# Fatigue_V1_00.net
KiCad netlist of a schematic drawn in Altium Designer
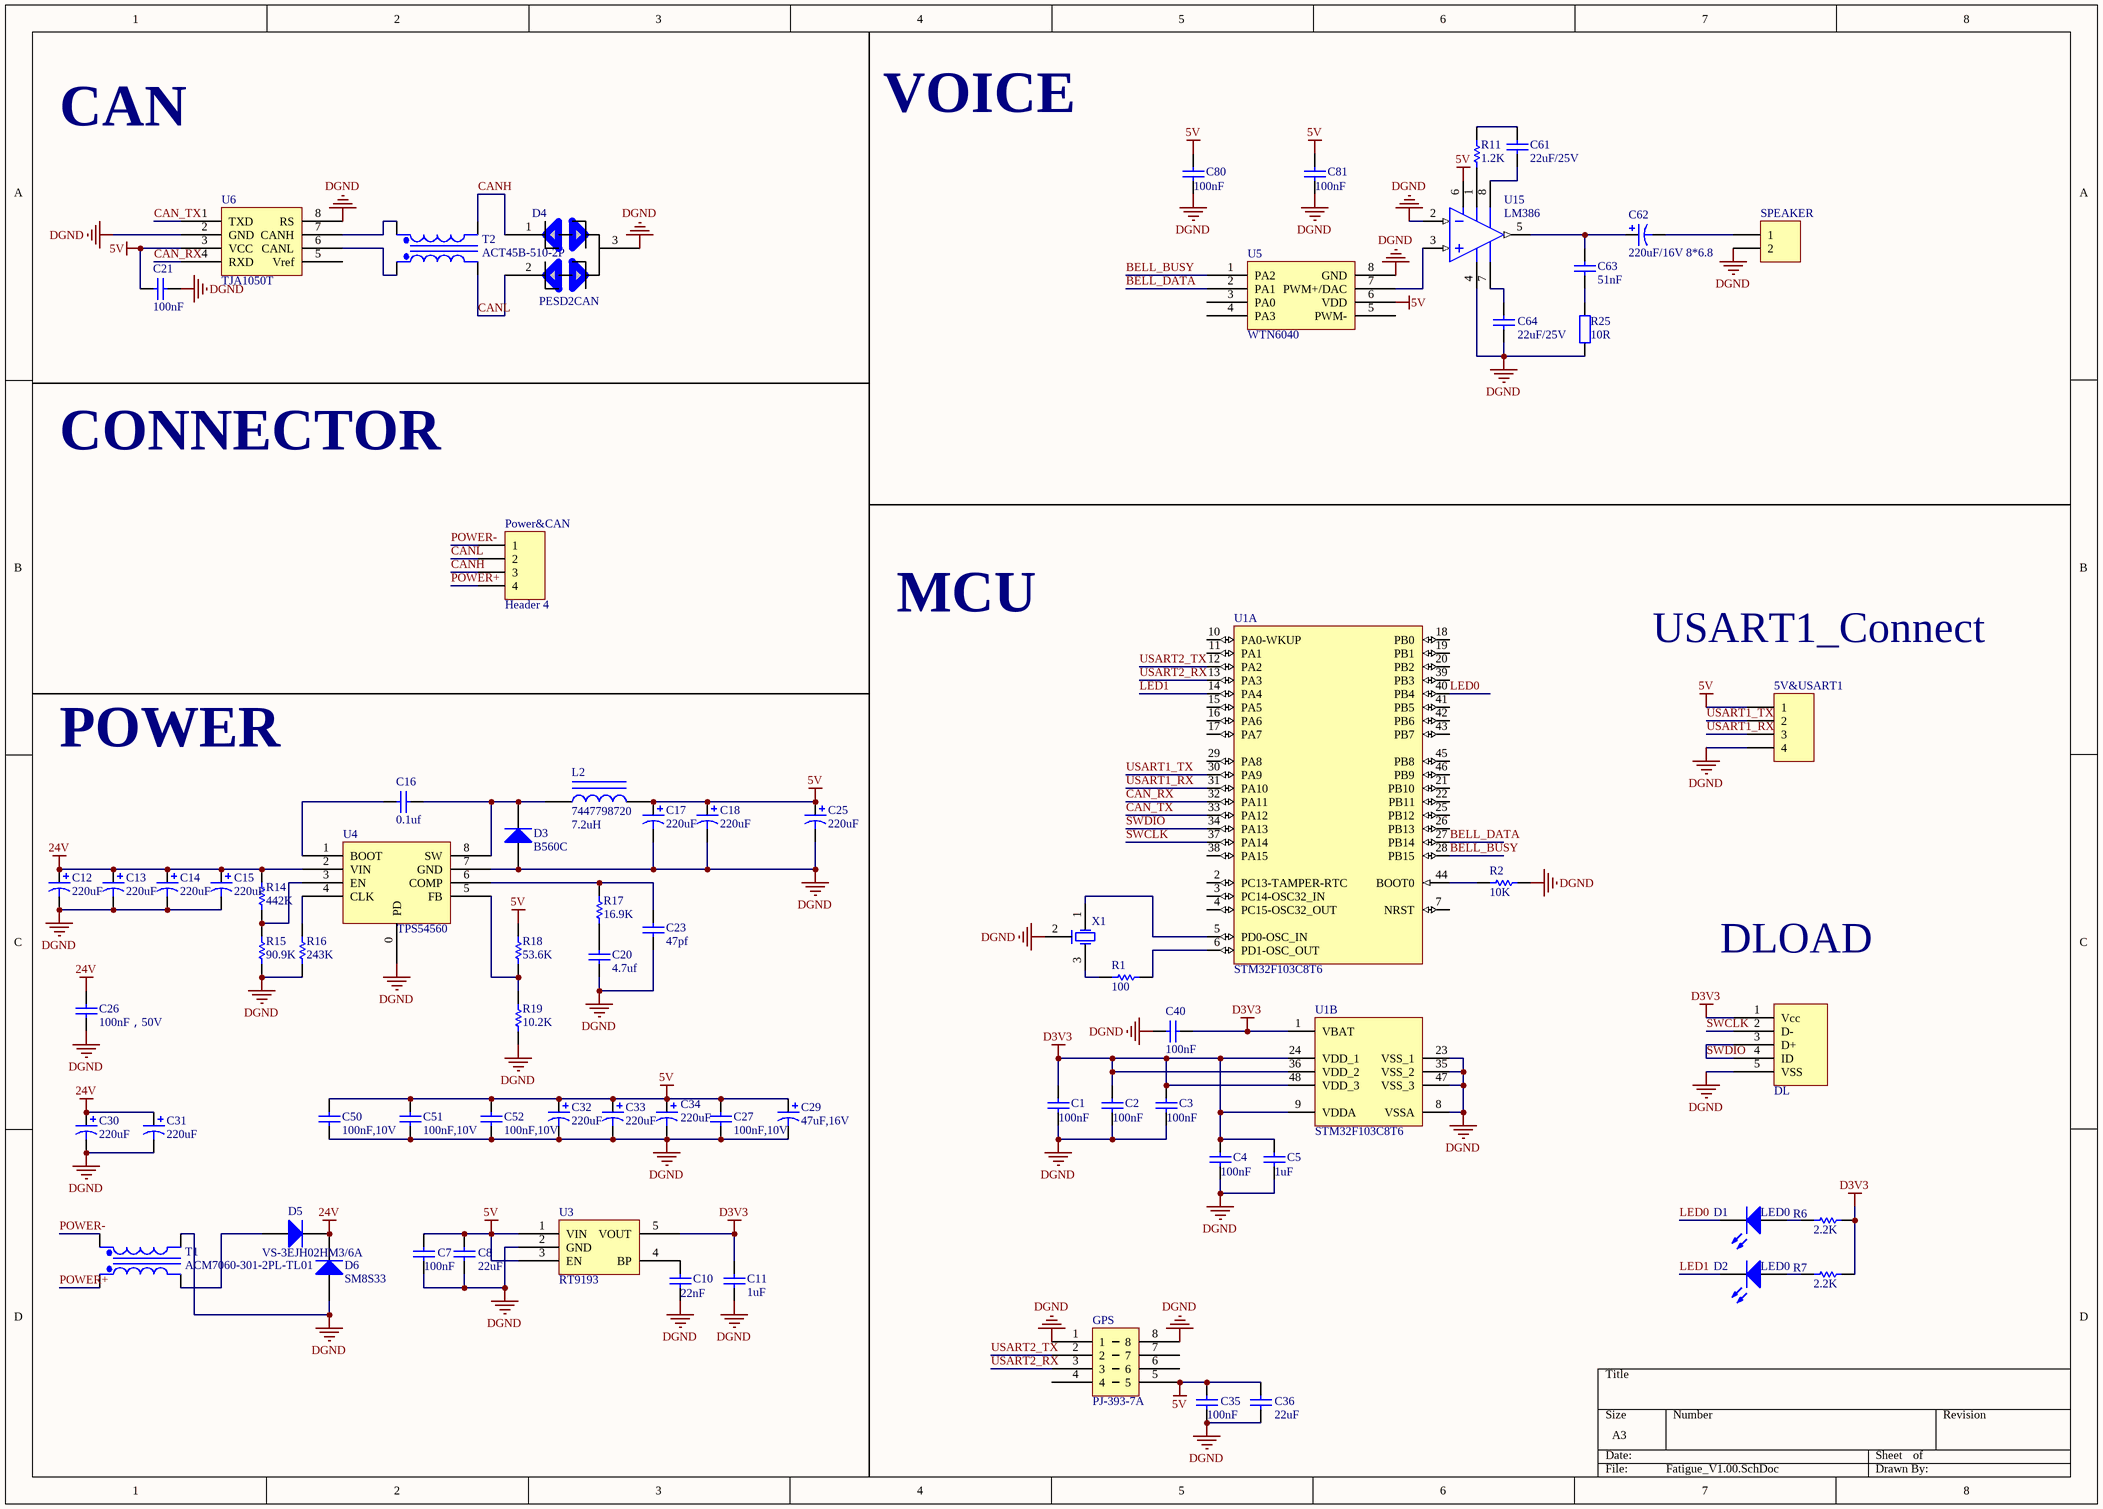
[diagram p0: Fatigue_V1.00.SchDoc]

(export (version "E")
  (design (tool "Eeschema 10.0.6"))
  (components
    (comp (ref "5V&USART1")
      (value "TEST_USART2")
      (footprint "HDR1X4")
      (description "Header, 4-Pin")
      (fields (field (name "PUBLISHER") "Altium Limited"))
      (libsource (lib "Miscellaneous Connectors") (part "Header 4"))
    )
    (comp (ref "C1")
      (value "100nF")
      (footprint "BinFeng:0402")
      (description "Capacitor")
      (fields (field (name "PUBLISHER") "Altium Limited"))
      (libsource (lib "Miscellaneous Devices") (part "Cap"))
    )
    (comp (ref "C2")
      (value "100nF")
      (footprint "BinFeng:0402")
      (description "Capacitor")
      (fields (field (name "PUBLISHER") "Altium Limited"))
      (libsource (lib "Miscellaneous Devices") (part "Cap"))
    )
    (comp (ref "C3")
      (value "100nF")
      (footprint "BinFeng:0402")
      (description "Capacitor")
      (fields (field (name "PUBLISHER") "Altium Limited"))
      (libsource (lib "Miscellaneous Devices") (part "Cap"))
    )
    (comp (ref "C4")
      (value "100nF")
      (footprint "BinFeng:0402")
      (description "Capacitor")
      (fields (field (name "PUBLISHER") "Altium Limited"))
      (libsource (lib "Miscellaneous Devices") (part "Cap"))
    )
    (comp (ref "C5")
      (value "1uF")
      (footprint "BinFeng:0603")
      (description "Capacitor")
      (fields (field (name "PUBLISHER") "Altium Limited"))
      (libsource (lib "Miscellaneous Devices") (part "Cap"))
    )
    (comp (ref "C7")
      (value "100nF")
      (footprint "BinFeng:0402")
      (description "Capacitor,100V")
      (fields (field (name "PUBLISHER") "Altium Limited"))
      (libsource (lib "Miscellaneous Devices") (part "Cap"))
    )
    (comp (ref "C8")
      (value "22uF")
      (footprint "0805")
      (description "Capacitor")
      (fields (field (name "PUBLISHER") "Altium Limited"))
      (libsource (lib "Miscellaneous Devices") (part "Cap"))
    )
    (comp (ref "C10")
      (value "22nF")
      (footprint "BinFeng:0402")
      (description "Capacitor")
      (fields (field (name "PUBLISHER") "Altium Limited"))
      (libsource (lib "Miscellaneous Devices") (part "Cap"))
    )
    (comp (ref "C11")
      (value "1uF")
      (footprint "BinFeng:0603")
      (description "Capacitor")
      (fields (field (name "PUBLISHER") "Altium Limited"))
      (libsource (lib "Miscellaneous Devices") (part "Cap"))
    )
    (comp (ref "C12")
      (value "220uF")
      (footprint "cap_pol_8*10.2")
      (description "Polarized Capacitor (Radial)")
      (fields (field (name "PUBLISHER") "Altium Limited"))
      (libsource (lib "Miscellaneous Devices") (part "Cap Pol1"))
    )
    (comp (ref "C13")
      (value "220uF")
      (footprint "cap_pol_8*10.2")
      (description "Polarized Capacitor (Radial)")
      (fields (field (name "PUBLISHER") "Altium Limited"))
      (libsource (lib "Miscellaneous Devices") (part "Cap Pol1"))
    )
    (comp (ref "C14")
      (value "220uF")
      (footprint "cap_pol_8*10.2")
      (description "Polarized Capacitor (Radial)")
      (fields (field (name "PUBLISHER") "Altium Limited"))
      (libsource (lib "Miscellaneous Devices") (part "Cap Pol1"))
    )
    (comp (ref "C15")
      (value "220uF")
      (footprint "cap_pol_8*10.2")
      (description "Polarized Capacitor (Radial)")
      (fields (field (name "PUBLISHER") "Altium Limited"))
      (libsource (lib "Miscellaneous Devices") (part "Cap Pol1"))
    )
    (comp (ref "C16")
      (value "0.1uf")
      (footprint "0603")
      (description "Capacitor")
      (fields (field (name "PUBLISHER") "Altium Limited"))
      (libsource (lib "Miscellaneous Devices") (part "Cap"))
    )
    (comp (ref "C17")
      (value "220uF")
      (footprint "cap_pol_8*10.2")
      (description "Polarized Capacitor (Radial)")
      (fields (field (name "PUBLISHER") "Altium Limited"))
      (libsource (lib "Miscellaneous Devices") (part "Cap Pol1"))
    )
    (comp (ref "C18")
      (value "220uF")
      (footprint "cap_pol_8*10.2")
      (description "Polarized Capacitor (Radial)")
      (fields (field (name "PUBLISHER") "Altium Limited"))
      (libsource (lib "Miscellaneous Devices") (part "Cap Pol1"))
    )
    (comp (ref "C20")
      (value "4.7uf")
      (footprint "0603")
      (description "Capacitor")
      (fields (field (name "PUBLISHER") "Altium Limited"))
      (libsource (lib "Miscellaneous Devices") (part "Cap"))
    )
    (comp (ref "C21")
      (value "100nF")
      (footprint "BinFeng:0402")
      (description "Capacitor")
      (fields (field (name "PUBLISHER") "Altium Limited"))
      (libsource (lib "Miscellaneous Devices") (part "Cap"))
    )
    (comp (ref "C23")
      (value "47pf")
      (footprint "0603")
      (description "Capacitor")
      (fields (field (name "PUBLISHER") "Altium Limited"))
      (libsource (lib "Miscellaneous Devices") (part "Cap"))
    )
    (comp (ref "C25")
      (value "220uF")
      (footprint "cap_pol_8*10.2")
      (description "Polarized Capacitor (Radial)")
      (fields (field (name "PUBLISHER") "Altium Limited"))
      (libsource (lib "Miscellaneous Devices") (part "Cap Pol1"))
    )
    (comp (ref "C26")
      (value "100nF，50V")
      (footprint "BinFeng:0603")
      (description "Capacitor")
      (fields (field (name "PUBLISHER") "Altium Limited"))
      (libsource (lib "Miscellaneous Devices") (part "Cap"))
    )
    (comp (ref "C27")
      (value "100nF,10V")
      (footprint "BinFeng:0402")
      (description "Capacitor")
      (fields (field (name "PUBLISHER") "Altium Limited"))
      (libsource (lib "Miscellaneous Devices") (part "Cap"))
    )
    (comp (ref "C29")
      (value "47uF,16V")
      (footprint "6032_pol")
      (description "Polarized Capacitor (Radial)")
      (fields (field (name "PUBLISHER") "Altium Limited"))
      (libsource (lib "Miscellaneous Devices") (part "Cap Pol1"))
    )
    (comp (ref "C30")
      (value "220uF")
      (footprint "cap_pol_8*10.2")
      (description "Polarized Capacitor (Radial)")
      (fields (field (name "PUBLISHER") "Altium Limited"))
      (libsource (lib "Miscellaneous Devices") (part "Cap Pol1"))
    )
    (comp (ref "C31")
      (value "220uF")
      (footprint "cap_pol_8*10.2")
      (description "Polarized Capacitor (Radial)")
      (fields (field (name "PUBLISHER") "Altium Limited"))
      (libsource (lib "Miscellaneous Devices") (part "Cap Pol1"))
    )
    (comp (ref "C32")
      (value "220uF")
      (footprint "cap_pol_8*10.2")
      (description "Polarized Capacitor (Radial)")
      (fields (field (name "PUBLISHER") "Altium Limited"))
      (libsource (lib "Miscellaneous Devices") (part "Cap Pol1"))
    )
    (comp (ref "C33")
      (value "220uF")
      (footprint "cap_pol_8*10.2")
      (description "Polarized Capacitor (Radial)")
      (fields (field (name "PUBLISHER") "Altium Limited"))
      (libsource (lib "Miscellaneous Devices") (part "Cap Pol1"))
    )
    (comp (ref "C34")
      (value "220uF")
      (footprint "cap_pol_8*10.2")
      (description "Polarized Capacitor (Radial)")
      (fields (field (name "PUBLISHER") "Altium Limited"))
      (libsource (lib "Miscellaneous Devices") (part "Cap Pol1"))
    )
    (comp (ref "C35")
      (value "100nF")
      (footprint "BinFeng:0402")
      (description "Capacitor,100V")
      (fields (field (name "PUBLISHER") "Altium Limited"))
      (libsource (lib "Miscellaneous Devices") (part "Cap"))
    )
    (comp (ref "C36")
      (value "22uF")
      (footprint "0805")
      (description "Capacitor")
      (fields (field (name "PUBLISHER") "Altium Limited"))
      (libsource (lib "Miscellaneous Devices") (part "Cap"))
    )
    (comp (ref "C40")
      (value "100nF")
      (footprint "BinFeng:0402")
      (description "Capacitor")
      (fields (field (name "PUBLISHER") "Altium Limited"))
      (libsource (lib "Miscellaneous Devices") (part "Cap"))
    )
    (comp (ref "C50")
      (value "100nF,10V")
      (footprint "BinFeng:0402")
      (description "Capacitor")
      (fields (field (name "PUBLISHER") "Altium Limited"))
      (libsource (lib "Miscellaneous Devices") (part "Cap"))
    )
    (comp (ref "C51")
      (value "100nF,10V")
      (footprint "BinFeng:0402")
      (description "Capacitor")
      (fields (field (name "PUBLISHER") "Altium Limited"))
      (libsource (lib "Miscellaneous Devices") (part "Cap"))
    )
    (comp (ref "C52")
      (value "100nF,10V")
      (footprint "BinFeng:0402")
      (description "Capacitor")
      (fields (field (name "PUBLISHER") "Altium Limited"))
      (libsource (lib "Miscellaneous Devices") (part "Cap"))
    )
    (comp (ref "C61")
      (value "22uF/25V")
      (footprint "0805")
      (description "Capacitor")
      (fields (field (name "PUBLISHER") "Altium Limited"))
      (libsource (lib "Miscellaneous Devices") (part "Cap"))
    )
    (comp (ref "C62")
      (value "220uF/16V 8*6.8")
      (footprint "cap_pol_8*10.2")
      (description "Polarized Capacitor (Radial)")
      (fields (field (name "PUBLISHER") "Altium Limited"))
      (libsource (lib "Miscellaneous Devices") (part "Cap Pol1"))
    )
    (comp (ref "C63")
      (value "51nF")
      (footprint "BinFeng:0402")
      (description "Capacitor")
      (fields (field (name "PUBLISHER") "Altium Limited"))
      (libsource (lib "Miscellaneous Devices") (part "Cap"))
    )
    (comp (ref "C64")
      (value "22uF/25V")
      (footprint "0805")
      (description "Capacitor")
      (fields (field (name "PUBLISHER") "Altium Limited"))
      (libsource (lib "Miscellaneous Devices") (part "Cap"))
    )
    (comp (ref "C80")
      (value "100nF")
      (footprint "BinFeng:0402")
      (description "Capacitor")
      (fields (field (name "PUBLISHER") "Altium Limited"))
      (libsource (lib "Miscellaneous Devices") (part "Cap"))
    )
    (comp (ref "C81")
      (value "100nF")
      (footprint "BinFeng:0402")
      (description "Capacitor")
      (fields (field (name "PUBLISHER") "Altium Limited"))
      (libsource (lib "Miscellaneous Devices") (part "Cap"))
    )
    (comp (ref "D1")
      (value "LED0")
      (footprint "1206_LED")
      (description "green LED")
      (fields (field (name "PUBLISHER") "Altium Limited"))
      (libsource (lib "Miscellaneous Devices") (part "LED0"))
    )
    (comp (ref "D2")
      (value "LED0")
      (footprint "1206_LED")
      (description "green LED")
      (fields (field (name "PUBLISHER") "Altium Limited"))
      (libsource (lib "Miscellaneous Devices") (part "LED0"))
    )
    (comp (ref "D3")
      (value "B560C")
      (footprint "BinFeng:SMC")
      (description "1 Amp General Purpose Rectifier")
      (fields (field (name "PUBLISHER") "Altium Limited"))
      (libsource (lib "Miscellaneous Devices") (part "Diode 1N4007"))
    )
    (comp (ref "D4")
      (value "PESD2CAN")
      (footprint "SOT23")
      (libsource (lib "BinFeng_Connectors") (part "PESD1CAN"))
    )
    (comp (ref "D5")
      (value "VS-3EJH02HM3/6A")
      (footprint "back:B290")
      (description "1 Amp General Purpose Rectifier")
      (fields (field (name "PUBLISHER") "Altium Limited"))
      (libsource (lib "Miscellaneous Devices") (part "Diode 1N4007"))
    )
    (comp (ref "D6")
      (value "SM8S33")
      (footprint "SM8S")
      (description "1 Amp General Purpose Rectifier")
      (fields (field (name "PUBLISHER") "Altium Limited"))
      (libsource (lib "Miscellaneous Devices") (part "Diode 1N4007"))
    )
    (comp (ref "DL")
      (value "USB_5pin")
      (footprint "USBmicro_B")
      (libsource (lib "BinFeng_Connectors") (part "USB_5pin"))
    )
    (comp (ref "GPS")
      (value "PJ-393-7A")
      (footprint "3.5mm earphone slot")
      (libsource (lib "BinFeng_IC") (part "3.5mm earphone slot"))
    )
    (comp (ref "L2")
      (value "7447798720")
      (footprint "1064")
      (description "Magnetic-Core Inductor")
      (fields (field (name "ALTIUM_VALUE") "7.2uH") (field (name "PUBLISHER") "Altium Limited"))
      (libsource (lib "Miscellaneous Devices") (part "Inductor Iron"))
    )
    (comp (ref "Power&CAN")
      (value "Header 4")
      (footprint "HDR1X4")
      (description "Header, 4-Pin")
      (fields (field (name "PUBLISHER") "Altium Limited"))
      (libsource (lib "Miscellaneous Connectors") (part "Header 4"))
    )
    (comp (ref "R1")
      (value "100")
      (footprint "BinFeng:0402")
      (description "Resistor")
      (fields (field (name "PUBLISHER") "Altium Limited"))
      (libsource (lib "Miscellaneous Devices") (part "Res1"))
    )
    (comp (ref "R2")
      (value "10K")
      (footprint "BinFeng:0402")
      (description "Resistor")
      (fields (field (name "PUBLISHER") "Altium Limited"))
      (libsource (lib "Miscellaneous Devices") (part "Res1"))
    )
    (comp (ref "R6")
      (value "2.2K")
      (footprint "BinFeng:0402")
      (description "Resistor")
      (fields (field (name "PUBLISHER") "Altium Limited"))
      (libsource (lib "Miscellaneous Devices") (part "Res1"))
    )
    (comp (ref "R7")
      (value "2.2K")
      (footprint "BinFeng:0402")
      (description "Resistor")
      (fields (field (name "PUBLISHER") "Altium Limited"))
      (libsource (lib "Miscellaneous Devices") (part "Res1"))
    )
    (comp (ref "R11")
      (value "1.2K")
      (footprint "BinFeng:0402")
      (description "Semiconductor Resistor")
      (fields (field (name "PUBLISHER") "Altium Limited"))
      (libsource (lib "Miscellaneous Devices") (part "Res Semi"))
    )
    (comp (ref "R14")
      (value "442K")
      (footprint "back:0603")
      (description "Resistor")
      (fields (field (name "PUBLISHER") "Altium Limited"))
      (libsource (lib "Miscellaneous Devices") (part "Res1"))
    )
    (comp (ref "R15")
      (value "90.9K")
      (footprint "back:0603")
      (description "Resistor")
      (fields (field (name "PUBLISHER") "Altium Limited"))
      (libsource (lib "Miscellaneous Devices") (part "Res1"))
    )
    (comp (ref "R16")
      (value "243K")
      (footprint "back:0603")
      (description "Resistor")
      (fields (field (name "PUBLISHER") "Altium Limited"))
      (libsource (lib "Miscellaneous Devices") (part "Res1"))
    )
    (comp (ref "R17")
      (value "16.9K")
      (footprint "back:0603")
      (description "Resistor")
      (fields (field (name "PUBLISHER") "Altium Limited"))
      (libsource (lib "Miscellaneous Devices") (part "Res1"))
    )
    (comp (ref "R18")
      (value "53.6K")
      (footprint "back:0603")
      (description "Resistor")
      (fields (field (name "PUBLISHER") "Altium Limited"))
      (libsource (lib "Miscellaneous Devices") (part "Res1"))
    )
    (comp (ref "R19")
      (value "10.2K")
      (footprint "back:0603")
      (description "Resistor")
      (fields (field (name "PUBLISHER") "Altium Limited"))
      (libsource (lib "Miscellaneous Devices") (part "Res1"))
    )
    (comp (ref "R25")
      (value "10R")
      (footprint "BinFeng:0402")
      (description "Resistor")
      (fields (field (name "PUBLISHER") "Altium Limited"))
      (libsource (lib "Miscellaneous Devices") (part "Res2"))
    )
    (comp (ref "SPEAKER")
      (value "SPEAKER")
      (footprint "HDR1X2")
      (description "Header, 2-Pin")
      (fields (field (name "PUBLISHER") "Altium Limited"))
      (libsource (lib "Miscellaneous Connectors") (part "Header 2"))
    )
    (comp (ref "T1")
      (value "ACM7060-301-2PL-TL01")
      (footprint "ACM7060-301-2P-TL01")
      (description "Transformer (Equivalent Circuit Model)")
      (fields (field (name "PUBLISHER") "Altium Limited"))
      (libsource (lib "Miscellaneous Devices") (part "Trans Eq"))
    )
    (comp (ref "T2")
      (value "ACT45B-510-2P")
      (footprint "ACT45B-510-2P")
      (description "Transformer (Equivalent Circuit Model)")
      (fields (field (name "PUBLISHER") "Altium Limited"))
      (libsource (lib "Miscellaneous Devices") (part "Trans Eq"))
    )
    (comp (ref "U1")
      (value "STM32F103C8T6")
      (footprint "STM-LQFP48_N")
      (libsource (lib "STMicroelectronics STM32 F1") (part "STM32F103C8T6"))
    )
    (comp (ref "U3") (value "RT9193") (footprint "SOT-23-5") (libsource (lib "BinFeng_IC") (part "RT9193")))
    (comp (ref "U4") (value "TPS54560") (footprint "HSOIC_8") (libsource (lib "MySchlib1") (part "TPS54560")))
    (comp (ref "U5") (value "WTN6040") (footprint "SO8") (libsource (lib "Schlib3") (part "WTN6040")))
    (comp (ref "U6")
      (value "TJA1050T")
      (footprint "SO8")
      (description "CAN Tranceiver")
      (libsource (lib "BinFeng_IC") (part "TJA1050T"))
    )
    (comp (ref "U15") (value "LM386") (footprint "SO8") (libsource (lib "My_Schlib") (part "LM386_1")))
    (comp (ref "X1") (value "8M smd") (footprint "8M") (libsource (lib "Schlib1") (part "8M smd")))
  )
  (nets
    (net (code "1") (name "/BELL_BUSY") (class "Default")
      (node (ref "U1") (pin "28") (pinfunction "PB15_28") (pintype "bidirectional"))
      (node (ref "U5") (pin "1") (pinfunction "PA2_1") (pintype "passive"))
    )
    (net (code "2") (name "/BELL_DATA") (class "Default")
      (node (ref "U1") (pin "27") (pinfunction "PB14_27") (pintype "bidirectional"))
      (node (ref "U5") (pin "2") (pinfunction "PA1_2") (pintype "passive"))
    )
    (net (code "3") (name "/CANH") (class "Default")
      (node (ref "D4") (pin "1") (pinfunction "11_1") (pintype "passive"))
      (node (ref "Power&CAN") (pin "3") (pinfunction "3_3") (pintype "passive"))
      (node (ref "T2") (pin "4") (pinfunction "Sec-_4") (pintype "passive"))
    )
    (net (code "4") (name "/CANL") (class "Default")
      (node (ref "D4") (pin "2") (pinfunction "12_2") (pintype "passive"))
      (node (ref "Power&CAN") (pin "2") (pinfunction "2_2") (pintype "passive"))
      (node (ref "T2") (pin "2") (pinfunction "Pri-_2") (pintype "passive"))
    )
    (net (code "5") (name "/CAN_RX") (class "Default")
      (node (ref "U1") (pin "32") (pinfunction "PA11_32") (pintype "bidirectional"))
      (node (ref "U6") (pin "4") (pinfunction "RXD_4") (pintype "passive"))
    )
    (net (code "6") (name "/CAN_TX") (class "Default")
      (node (ref "U1") (pin "33") (pinfunction "PA12_33") (pintype "bidirectional"))
      (node (ref "U6") (pin "1") (pinfunction "TXD_1") (pintype "passive"))
    )
    (net (code "7") (name "/LED0") (class "Default")
      (node (ref "D1") (pin "2") (pinfunction "K_2") (pintype "passive"))
      (node (ref "U1") (pin "40") (pinfunction "PB4_40") (pintype "bidirectional"))
    )
    (net (code "8") (name "/LED1") (class "Default")
      (node (ref "D2") (pin "2") (pinfunction "K_2") (pintype "passive"))
      (node (ref "U1") (pin "14") (pinfunction "PA4_14") (pintype "bidirectional"))
    )
    (net (code "9") (name "/POWER+") (class "Default")
      (node (ref "Power&CAN") (pin "4") (pinfunction "4_4") (pintype "passive"))
      (node (ref "T1") (pin "1") (pinfunction "Pri+_1") (pintype "passive"))
    )
    (net (code "10") (name "/POWER-") (class "Default")
      (node (ref "Power&CAN") (pin "1") (pinfunction "1_1") (pintype "passive"))
      (node (ref "T1") (pin "3") (pinfunction "Sec+_3") (pintype "passive"))
    )
    (net (code "11") (name "/SWCLK") (class "Default")
      (node (ref "DL") (pin "2") (pinfunction "D-_2") (pintype "passive"))
      (node (ref "U1") (pin "37") (pinfunction "PA14_37") (pintype "bidirectional"))
    )
    (net (code "12") (name "/SWDIO") (class "Default")
      (node (ref "DL") (pin "3") (pinfunction "D+_3") (pintype "passive"))
      (node (ref "DL") (pin "4") (pinfunction "ID_4") (pintype "passive"))
      (node (ref "U1") (pin "34") (pinfunction "PA13_34") (pintype "bidirectional"))
    )
    (net (code "13") (name "/USART1_RX") (class "Default")
      (node (ref "5V&USART1") (pin "3") (pinfunction "3_3") (pintype "passive"))
      (node (ref "U1") (pin "31") (pinfunction "PA10_31") (pintype "bidirectional"))
    )
    (net (code "14") (name "/USART1_TX") (class "Default")
      (node (ref "5V&USART1") (pin "2") (pinfunction "2_2") (pintype "passive"))
      (node (ref "U1") (pin "30") (pinfunction "PA9_30") (pintype "bidirectional"))
    )
    (net (code "15") (name "/USART2_RX") (class "Default")
      (node (ref "GPS") (pin "3") (pinfunction "3_3") (pintype "passive"))
      (node (ref "U1") (pin "13") (pinfunction "PA3_13") (pintype "bidirectional"))
    )
    (net (code "16") (name "/USART2_TX") (class "Default")
      (node (ref "GPS") (pin "2") (pinfunction "2_2") (pintype "passive"))
      (node (ref "U1") (pin "12") (pinfunction "PA2_12") (pintype "bidirectional"))
    )
    (net (code "17") (name "5V") (class "Default")
      (node (ref "5V&USART1") (pin "1") (pinfunction "1_1") (pintype "passive"))
      (node (ref "C17") (pin "1") (pinfunction "1_1") (pintype "passive"))
      (node (ref "C18") (pin "1") (pinfunction "1_1") (pintype "passive"))
      (node (ref "C21") (pin "1") (pinfunction "1_1") (pintype "passive"))
      (node (ref "C25") (pin "1") (pinfunction "1_1") (pintype "passive"))
      (node (ref "C27") (pin "1") (pinfunction "1_1") (pintype "passive"))
      (node (ref "C29") (pin "1") (pinfunction "1_1") (pintype "passive"))
      (node (ref "C32") (pin "1") (pinfunction "1_1") (pintype "passive"))
      (node (ref "C33") (pin "1") (pinfunction "1_1") (pintype "passive"))
      (node (ref "C34") (pin "1") (pinfunction "1_1") (pintype "passive"))
      (node (ref "C35") (pin "2") (pinfunction "2_2") (pintype "passive"))
      (node (ref "C36") (pin "2") (pinfunction "2_2") (pintype "passive"))
      (node (ref "C50") (pin "1") (pinfunction "1_1") (pintype "passive"))
      (node (ref "C51") (pin "1") (pinfunction "1_1") (pintype "passive"))
      (node (ref "C52") (pin "1") (pinfunction "1_1") (pintype "passive"))
      (node (ref "C7") (pin "2") (pinfunction "2_2") (pintype "passive"))
      (node (ref "C8") (pin "2") (pinfunction "2_2") (pintype "passive"))
      (node (ref "C80") (pin "2") (pinfunction "2_2") (pintype "passive"))
      (node (ref "C81") (pin "2") (pinfunction "2_2") (pintype "passive"))
      (node (ref "GPS") (pin "5") (pinfunction "5_5") (pintype "passive"))
      (node (ref "L2") (pin "2") (pinfunction "2_2") (pintype "passive"))
      (node (ref "R18") (pin "2") (pinfunction "2_2") (pintype "passive"))
      (node (ref "U15") (pin "6") (pinfunction "OS_NUL_6") (pintype "passive"))
      (node (ref "U3") (pin "1") (pinfunction "VIN_1") (pintype "passive"))
      (node (ref "U3") (pin "3") (pinfunction "EN_3") (pintype "passive"))
      (node (ref "U5") (pin "6") (pinfunction "VDD_6") (pintype "power_in"))
      (node (ref "U6") (pin "3") (pinfunction "VCC_3") (pintype "passive"))
    )
    (net (code "18") (name "24V") (class "Default")
      (node (ref "C12") (pin "1") (pinfunction "1_1") (pintype "passive"))
      (node (ref "C13") (pin "1") (pinfunction "1_1") (pintype "passive"))
      (node (ref "C14") (pin "1") (pinfunction "1_1") (pintype "passive"))
      (node (ref "C15") (pin "1") (pinfunction "1_1") (pintype "passive"))
      (node (ref "C26") (pin "1") (pinfunction "1_1") (pintype "passive"))
      (node (ref "C30") (pin "1") (pinfunction "1_1") (pintype "passive"))
      (node (ref "C31") (pin "1") (pinfunction "1_1") (pintype "passive"))
      (node (ref "D5") (pin "2") (pinfunction "K_2") (pintype "passive"))
      (node (ref "D6") (pin "2") (pinfunction "K_2") (pintype "passive"))
      (node (ref "R14") (pin "2") (pinfunction "2_2") (pintype "passive"))
      (node (ref "U4") (pin "2") (pinfunction "VIN_2") (pintype "passive"))
    )
    (net (code "19") (name "D3V3") (class "Default")
      (node (ref "C1") (pin "2") (pinfunction "2_2") (pintype "passive"))
      (node (ref "C11") (pin "2") (pinfunction "2_2") (pintype "passive"))
      (node (ref "C2") (pin "2") (pinfunction "2_2") (pintype "passive"))
      (node (ref "C3") (pin "2") (pinfunction "2_2") (pintype "passive"))
      (node (ref "C4") (pin "2") (pinfunction "2_2") (pintype "passive"))
      (node (ref "C40") (pin "1") (pinfunction "1_1") (pintype "passive"))
      (node (ref "C5") (pin "2") (pinfunction "2_2") (pintype "passive"))
      (node (ref "DL") (pin "1") (pinfunction "Vcc_1") (pintype "passive"))
      (node (ref "R6") (pin "1") (pinfunction "1_1") (pintype "passive"))
      (node (ref "R7") (pin "1") (pinfunction "1_1") (pintype "passive"))
      (node (ref "U1") (pin "1") (pinfunction "VBAT_1") (pintype "power_in"))
      (node (ref "U1") (pin "24") (pinfunction "VDD_1_24") (pintype "power_in"))
      (node (ref "U1") (pin "36") (pinfunction "VDD_2_36") (pintype "power_in"))
      (node (ref "U1") (pin "48") (pinfunction "VDD_3_48") (pintype "power_in"))
      (node (ref "U1") (pin "9") (pinfunction "VDDA_9") (pintype "power_in"))
      (node (ref "U3") (pin "5") (pinfunction "VOUT_5") (pintype "passive"))
    )
    (net (code "20") (name "DGND") (class "Default")
      (node (ref "5V&USART1") (pin "4") (pinfunction "4_4") (pintype "passive"))
      (node (ref "C1") (pin "1") (pinfunction "1_1") (pintype "passive"))
      (node (ref "C10") (pin "1") (pinfunction "1_1") (pintype "passive"))
      (node (ref "C11") (pin "1") (pinfunction "1_1") (pintype "passive"))
      (node (ref "C12") (pin "2") (pinfunction "2_2") (pintype "passive"))
      (node (ref "C13") (pin "2") (pinfunction "2_2") (pintype "passive"))
      (node (ref "C14") (pin "2") (pinfunction "2_2") (pintype "passive"))
      (node (ref "C15") (pin "2") (pinfunction "2_2") (pintype "passive"))
      (node (ref "C17") (pin "2") (pinfunction "2_2") (pintype "passive"))
      (node (ref "C18") (pin "2") (pinfunction "2_2") (pintype "passive"))
      (node (ref "C2") (pin "1") (pinfunction "1_1") (pintype "passive"))
      (node (ref "C20") (pin "2") (pinfunction "2_2") (pintype "passive"))
      (node (ref "C21") (pin "2") (pinfunction "2_2") (pintype "passive"))
      (node (ref "C23") (pin "2") (pinfunction "2_2") (pintype "passive"))
      (node (ref "C25") (pin "2") (pinfunction "2_2") (pintype "passive"))
      (node (ref "C26") (pin "2") (pinfunction "2_2") (pintype "passive"))
      (node (ref "C27") (pin "2") (pinfunction "2_2") (pintype "passive"))
      (node (ref "C29") (pin "2") (pinfunction "2_2") (pintype "passive"))
      (node (ref "C3") (pin "1") (pinfunction "1_1") (pintype "passive"))
      (node (ref "C30") (pin "2") (pinfunction "2_2") (pintype "passive"))
      (node (ref "C31") (pin "2") (pinfunction "2_2") (pintype "passive"))
      (node (ref "C32") (pin "2") (pinfunction "2_2") (pintype "passive"))
      (node (ref "C33") (pin "2") (pinfunction "2_2") (pintype "passive"))
      (node (ref "C34") (pin "2") (pinfunction "2_2") (pintype "passive"))
      (node (ref "C35") (pin "1") (pinfunction "1_1") (pintype "passive"))
      (node (ref "C36") (pin "1") (pinfunction "1_1") (pintype "passive"))
      (node (ref "C4") (pin "1") (pinfunction "1_1") (pintype "passive"))
      (node (ref "C40") (pin "2") (pinfunction "2_2") (pintype "passive"))
      (node (ref "C5") (pin "1") (pinfunction "1_1") (pintype "passive"))
      (node (ref "C50") (pin "2") (pinfunction "2_2") (pintype "passive"))
      (node (ref "C51") (pin "2") (pinfunction "2_2") (pintype "passive"))
      (node (ref "C52") (pin "2") (pinfunction "2_2") (pintype "passive"))
      (node (ref "C64") (pin "1") (pinfunction "1_1") (pintype "passive"))
      (node (ref "C7") (pin "1") (pinfunction "1_1") (pintype "passive"))
      (node (ref "C8") (pin "1") (pinfunction "1_1") (pintype "passive"))
      (node (ref "C80") (pin "1") (pinfunction "1_1") (pintype "passive"))
      (node (ref "C81") (pin "1") (pinfunction "1_1") (pintype "passive"))
      (node (ref "D3") (pin "1") (pinfunction "A_1") (pintype "passive"))
      (node (ref "D4") (pin "3") (pinfunction "13_3") (pintype "passive"))
      (node (ref "D6") (pin "1") (pinfunction "A_1") (pintype "passive"))
      (node (ref "DL") (pin "5") (pinfunction "VSS_5") (pintype "passive"))
      (node (ref "GPS") (pin "1") (pinfunction "1_1") (pintype "passive"))
      (node (ref "GPS") (pin "8") (pinfunction "8_8") (pintype "passive"))
      (node (ref "R15") (pin "1") (pinfunction "1_1") (pintype "passive"))
      (node (ref "R16") (pin "1") (pinfunction "1_1") (pintype "passive"))
      (node (ref "R19") (pin "1") (pinfunction "1_1") (pintype "passive"))
      (node (ref "R2") (pin "2") (pinfunction "2_2") (pintype "passive"))
      (node (ref "R25") (pin "1") (pinfunction "1_1") (pintype "passive"))
      (node (ref "SPEAKER") (pin "2") (pinfunction "2_2") (pintype "passive"))
      (node (ref "T1") (pin "4") (pinfunction "Sec-_4") (pintype "passive"))
      (node (ref "U1") (pin "23") (pinfunction "VSS_1_23") (pintype "power_in"))
      (node (ref "U1") (pin "35") (pinfunction "VSS_2_35") (pintype "power_in"))
      (node (ref "U1") (pin "47") (pinfunction "VSS_3_47") (pintype "power_in"))
      (node (ref "U1") (pin "8") (pinfunction "VSSA_8") (pintype "power_in"))
      (node (ref "U15") (pin "2") (pinfunction "IN-_2") (pintype "input"))
      (node (ref "U15") (pin "4") (pinfunction "V+_4") (pintype "power_in"))
      (node (ref "U3") (pin "2") (pinfunction "GND_2") (pintype "passive"))
      (node (ref "U4") (pin "0") (pinfunction "PD_0") (pintype "passive"))
      (node (ref "U4") (pin "7") (pinfunction "GND_7") (pintype "passive"))
      (node (ref "U5") (pin "8") (pinfunction "GND_8") (pintype "power_in"))
      (node (ref "U6") (pin "2") (pinfunction "GND_2") (pintype "passive"))
      (node (ref "U6") (pin "8") (pinfunction "RS_8") (pintype "passive"))
      (node (ref "X1") (pin "2") (pinfunction "GND_2") (pintype "passive"))
    )
    (net (code "21") (name "Net-(C20-Pad1)") (class "Default")
      (node (ref "C20") (pin "1") (pinfunction "1_1") (pintype "passive"))
      (node (ref "R17") (pin "1") (pinfunction "1_1") (pintype "passive"))
    )
    (net (code "22") (name "Net-(C61-Pad1)") (class "Default")
      (node (ref "C61") (pin "1") (pinfunction "1_1") (pintype "passive"))
      (node (ref "R11") (pin "1") (pinfunction "1_1") (pintype "passive"))
    )
    (net (code "23") (name "Net-(C61-Pad2)") (class "Default")
      (node (ref "C61") (pin "2") (pinfunction "2_2") (pintype "passive"))
      (node (ref "U15") (pin "8") (pinfunction "OS_NUL_8") (pintype "passive"))
    )
    (net (code "24") (name "Net-(C62-Pad2)") (class "Default")
      (node (ref "C62") (pin "2") (pinfunction "2_2") (pintype "passive"))
      (node (ref "SPEAKER") (pin "1") (pinfunction "1_1") (pintype "passive"))
    )
    (net (code "25") (name "Net-(C63-Pad2)") (class "Default")
      (node (ref "C63") (pin "2") (pinfunction "2_2") (pintype "passive"))
      (node (ref "R25") (pin "2") (pinfunction "2_2") (pintype "passive"))
    )
    (net (code "26") (name "Net-(D1-A)") (class "Default")
      (node (ref "D1") (pin "1") (pinfunction "A_1") (pintype "passive"))
      (node (ref "R6") (pin "2") (pinfunction "2_2") (pintype "passive"))
    )
    (net (code "27") (name "Net-(D2-A)") (class "Default")
      (node (ref "D2") (pin "1") (pinfunction "A_1") (pintype "passive"))
      (node (ref "R7") (pin "2") (pinfunction "2_2") (pintype "passive"))
    )
    (net (code "28") (name "Net-(D3-K)") (class "Default")
      (node (ref "C16") (pin "1") (pinfunction "1_1") (pintype "passive"))
      (node (ref "D3") (pin "2") (pinfunction "K_2") (pintype "passive"))
      (node (ref "L2") (pin "1") (pinfunction "1_1") (pintype "passive"))
      (node (ref "U4") (pin "8") (pinfunction "SW_8") (pintype "passive"))
    )
    (net (code "29") (name "Net-(D5-A)") (class "Default")
      (node (ref "D5") (pin "1") (pinfunction "A_1") (pintype "passive"))
      (node (ref "T1") (pin "2") (pinfunction "Pri-_2") (pintype "passive"))
    )
    (net (code "30") (name "Net-(T2-Pri+)") (class "Default")
      (node (ref "T2") (pin "1") (pinfunction "Pri+_1") (pintype "passive"))
      (node (ref "U6") (pin "6") (pinfunction "CANL_6") (pintype "passive"))
    )
    (net (code "31") (name "Net-(T2-Sec+)") (class "Default")
      (node (ref "T2") (pin "3") (pinfunction "Sec+_3") (pintype "passive"))
      (node (ref "U6") (pin "7") (pinfunction "CANH_7") (pintype "passive"))
    )
    (net (code "32") (name "Net-(U1A-BOOT0)") (class "Default")
      (node (ref "R2") (pin "1") (pinfunction "1_1") (pintype "passive"))
      (node (ref "U1") (pin "44") (pinfunction "BOOT0_44") (pintype "input"))
    )
    (net (code "33") (name "Net-(U1A-PD0-OSC_IN)") (class "Default")
      (node (ref "U1") (pin "5") (pinfunction "PD0-OSC_IN_5") (pintype "bidirectional"))
      (node (ref "X1") (pin "1") (pinfunction "OSC1_1") (pintype "passive"))
    )
    (net (code "34") (name "Net-(U1A-PD1-OSC_OUT)") (class "Default")
      (node (ref "R1") (pin "2") (pinfunction "2_2") (pintype "passive"))
      (node (ref "U1") (pin "6") (pinfunction "PD1-OSC_OUT_6") (pintype "bidirectional"))
    )
    (net (code "35") (name "Net-(U3-BP)") (class "Default")
      (node (ref "C10") (pin "2") (pinfunction "2_2") (pintype "passive"))
      (node (ref "U3") (pin "4") (pinfunction "BP_4") (pintype "passive"))
    )
    (net (code "36") (name "Net-(U4-BOOT)") (class "Default")
      (node (ref "C16") (pin "2") (pinfunction "2_2") (pintype "passive"))
      (node (ref "U4") (pin "1") (pinfunction "BOOT_1") (pintype "passive"))
    )
    (net (code "37") (name "Net-(U4-CLK)") (class "Default")
      (node (ref "R16") (pin "2") (pinfunction "2_2") (pintype "passive"))
      (node (ref "U4") (pin "4") (pinfunction "CLK_4") (pintype "passive"))
    )
    (net (code "38") (name "Net-(U4-COMP)") (class "Default")
      (node (ref "C23") (pin "1") (pinfunction "1_1") (pintype "passive"))
      (node (ref "R17") (pin "2") (pinfunction "2_2") (pintype "passive"))
      (node (ref "U4") (pin "6") (pinfunction "COMP_6") (pintype "passive"))
    )
    (net (code "39") (name "Net-(U4-EN)") (class "Default")
      (node (ref "R14") (pin "1") (pinfunction "1_1") (pintype "passive"))
      (node (ref "R15") (pin "2") (pinfunction "2_2") (pintype "passive"))
      (node (ref "U4") (pin "3") (pinfunction "EN_3") (pintype "passive"))
    )
    (net (code "40") (name "Net-(U4-FB)") (class "Default")
      (node (ref "R18") (pin "1") (pinfunction "1_1") (pintype "passive"))
      (node (ref "R19") (pin "2") (pinfunction "2_2") (pintype "passive"))
      (node (ref "U4") (pin "5") (pinfunction "FB_5") (pintype "passive"))
    )
    (net (code "41") (name "Net-(U15-IN+)") (class "Default")
      (node (ref "U15") (pin "3") (pinfunction "IN+_3") (pintype "input"))
      (node (ref "U5") (pin "7") (pinfunction "PWM+/DAC_7") (pintype "passive"))
    )
    (net (code "42") (name "Net-(U15-OUT)") (class "Default")
      (node (ref "C62") (pin "1") (pinfunction "1_1") (pintype "passive"))
      (node (ref "C63") (pin "1") (pinfunction "1_1") (pintype "passive"))
      (node (ref "U15") (pin "5") (pinfunction "OUT_5") (pintype "output"))
    )
    (net (code "43") (name "Net-(U15-TAB)") (class "Default")
      (node (ref "C64") (pin "2") (pinfunction "2_2") (pintype "passive"))
      (node (ref "U15") (pin "7") (pinfunction "TAB_7") (pintype "passive"))
    )
    (net (code "44") (name "Net-(U15-V-)") (class "Default")
      (node (ref "R11") (pin "2") (pinfunction "2_2") (pintype "passive"))
      (node (ref "U15") (pin "1") (pinfunction "V-_1") (pintype "power_in"))
    )
    (net (code "45") (name "Net-(X1-OSC2)") (class "Default")
      (node (ref "R1") (pin "1") (pinfunction "1_1") (pintype "passive"))
      (node (ref "X1") (pin "3") (pinfunction "OSC2_3") (pintype "passive"))
    )
    (net (code "46") (name "unconnected-(GPS-Pad4)") (class "Default")
      (node (ref "GPS") (pin "4") (pinfunction "4_4") (pintype "passive"))
    )
    (net (code "47") (name "unconnected-(GPS-Pad6)") (class "Default")
      (node (ref "GPS") (pin "6") (pinfunction "6_6") (pintype "passive"))
    )
    (net (code "48") (name "unconnected-(GPS-Pad7)") (class "Default")
      (node (ref "GPS") (pin "7") (pinfunction "7_7") (pintype "passive"))
    )
    (net (code "49") (name "unconnected-(U1A-NRST-Pad7)") (class "Default")
      (node (ref "U1") (pin "7") (pinfunction "NRST_7") (pintype "bidirectional"))
    )
    (net (code "50") (name "unconnected-(U1A-PA0-WKUP-Pad10)") (class "Default")
      (node (ref "U1") (pin "10") (pinfunction "PA0-WKUP_10") (pintype "bidirectional"))
    )
    (net (code "51") (name "unconnected-(U1A-PA1-Pad11)") (class "Default")
      (node (ref "U1") (pin "11") (pinfunction "PA1_11") (pintype "bidirectional"))
    )
    (net (code "52") (name "unconnected-(U1A-PA5-Pad15)") (class "Default")
      (node (ref "U1") (pin "15") (pinfunction "PA5_15") (pintype "bidirectional"))
    )
    (net (code "53") (name "unconnected-(U1A-PA6-Pad16)") (class "Default")
      (node (ref "U1") (pin "16") (pinfunction "PA6_16") (pintype "bidirectional"))
    )
    (net (code "54") (name "unconnected-(U1A-PA7-Pad17)") (class "Default")
      (node (ref "U1") (pin "17") (pinfunction "PA7_17") (pintype "bidirectional"))
    )
    (net (code "55") (name "unconnected-(U1A-PA8-Pad29)") (class "Default")
      (node (ref "U1") (pin "29") (pinfunction "PA8_29") (pintype "bidirectional"))
    )
    (net (code "56") (name "unconnected-(U1A-PA15-Pad38)") (class "Default")
      (node (ref "U1") (pin "38") (pinfunction "PA15_38") (pintype "bidirectional"))
    )
    (net (code "57") (name "unconnected-(U1A-PB0-Pad18)") (class "Default")
      (node (ref "U1") (pin "18") (pinfunction "PB0_18") (pintype "bidirectional"))
    )
    (net (code "58") (name "unconnected-(U1A-PB1-Pad19)") (class "Default")
      (node (ref "U1") (pin "19") (pinfunction "PB1_19") (pintype "bidirectional"))
    )
    (net (code "59") (name "unconnected-(U1A-PB2-Pad20)") (class "Default")
      (node (ref "U1") (pin "20") (pinfunction "PB2_20") (pintype "bidirectional"))
    )
    (net (code "60") (name "unconnected-(U1A-PB3-Pad39)") (class "Default")
      (node (ref "U1") (pin "39") (pinfunction "PB3_39") (pintype "bidirectional"))
    )
    (net (code "61") (name "unconnected-(U1A-PB5-Pad41)") (class "Default")
      (node (ref "U1") (pin "41") (pinfunction "PB5_41") (pintype "bidirectional"))
    )
    (net (code "62") (name "unconnected-(U1A-PB6-Pad42)") (class "Default")
      (node (ref "U1") (pin "42") (pinfunction "PB6_42") (pintype "bidirectional"))
    )
    (net (code "63") (name "unconnected-(U1A-PB7-Pad43)") (class "Default")
      (node (ref "U1") (pin "43") (pinfunction "PB7_43") (pintype "bidirectional"))
    )
    (net (code "64") (name "unconnected-(U1A-PB8-Pad45)") (class "Default")
      (node (ref "U1") (pin "45") (pinfunction "PB8_45") (pintype "bidirectional"))
    )
    (net (code "65") (name "unconnected-(U1A-PB9-Pad46)") (class "Default")
      (node (ref "U1") (pin "46") (pinfunction "PB9_46") (pintype "bidirectional"))
    )
    (net (code "66") (name "unconnected-(U1A-PB10-Pad21)") (class "Default")
      (node (ref "U1") (pin "21") (pinfunction "PB10_21") (pintype "bidirectional"))
    )
    (net (code "67") (name "unconnected-(U1A-PB11-Pad22)") (class "Default")
      (node (ref "U1") (pin "22") (pinfunction "PB11_22") (pintype "bidirectional"))
    )
    (net (code "68") (name "unconnected-(U1A-PB12-Pad25)") (class "Default")
      (node (ref "U1") (pin "25") (pinfunction "PB12_25") (pintype "bidirectional"))
    )
    (net (code "69") (name "unconnected-(U1A-PB13-Pad26)") (class "Default")
      (node (ref "U1") (pin "26") (pinfunction "PB13_26") (pintype "bidirectional"))
    )
    (net (code "70") (name "unconnected-(U1A-PC13-TAMPER-RTC-Pad2)") (class "Default")
      (node (ref "U1") (pin "2") (pinfunction "PC13-TAMPER-RTC_2") (pintype "bidirectional"))
    )
    (net (code "71") (name "unconnected-(U1A-PC14-OSC32_IN-Pad3)") (class "Default")
      (node (ref "U1") (pin "3") (pinfunction "PC14-OSC32_IN_3") (pintype "bidirectional"))
    )
    (net (code "72") (name "unconnected-(U1A-PC15-OSC32_OUT-Pad4)") (class "Default")
      (node (ref "U1") (pin "4") (pinfunction "PC15-OSC32_OUT_4") (pintype "bidirectional"))
    )
    (net (code "73") (name "unconnected-(U5-PA0-Pad3)") (class "Default")
      (node (ref "U5") (pin "3") (pinfunction "PA0_3") (pintype "passive"))
    )
    (net (code "74") (name "unconnected-(U5-PA3-Pad4)") (class "Default")
      (node (ref "U5") (pin "4") (pinfunction "PA3_4") (pintype "passive"))
    )
    (net (code "75") (name "unconnected-(U5-PWM--Pad5)") (class "Default")
      (node (ref "U5") (pin "5") (pinfunction "PWM-_5") (pintype "passive"))
    )
    (net (code "76") (name "unconnected-(U6-Vref-Pad5)") (class "Default")
      (node (ref "U6") (pin "5") (pinfunction "Vref_5") (pintype "passive"))
    )
  )
)
